# SCH__0_1_2022-09-27.net
KiCad netlist of a schematic drawn in EasyEDA
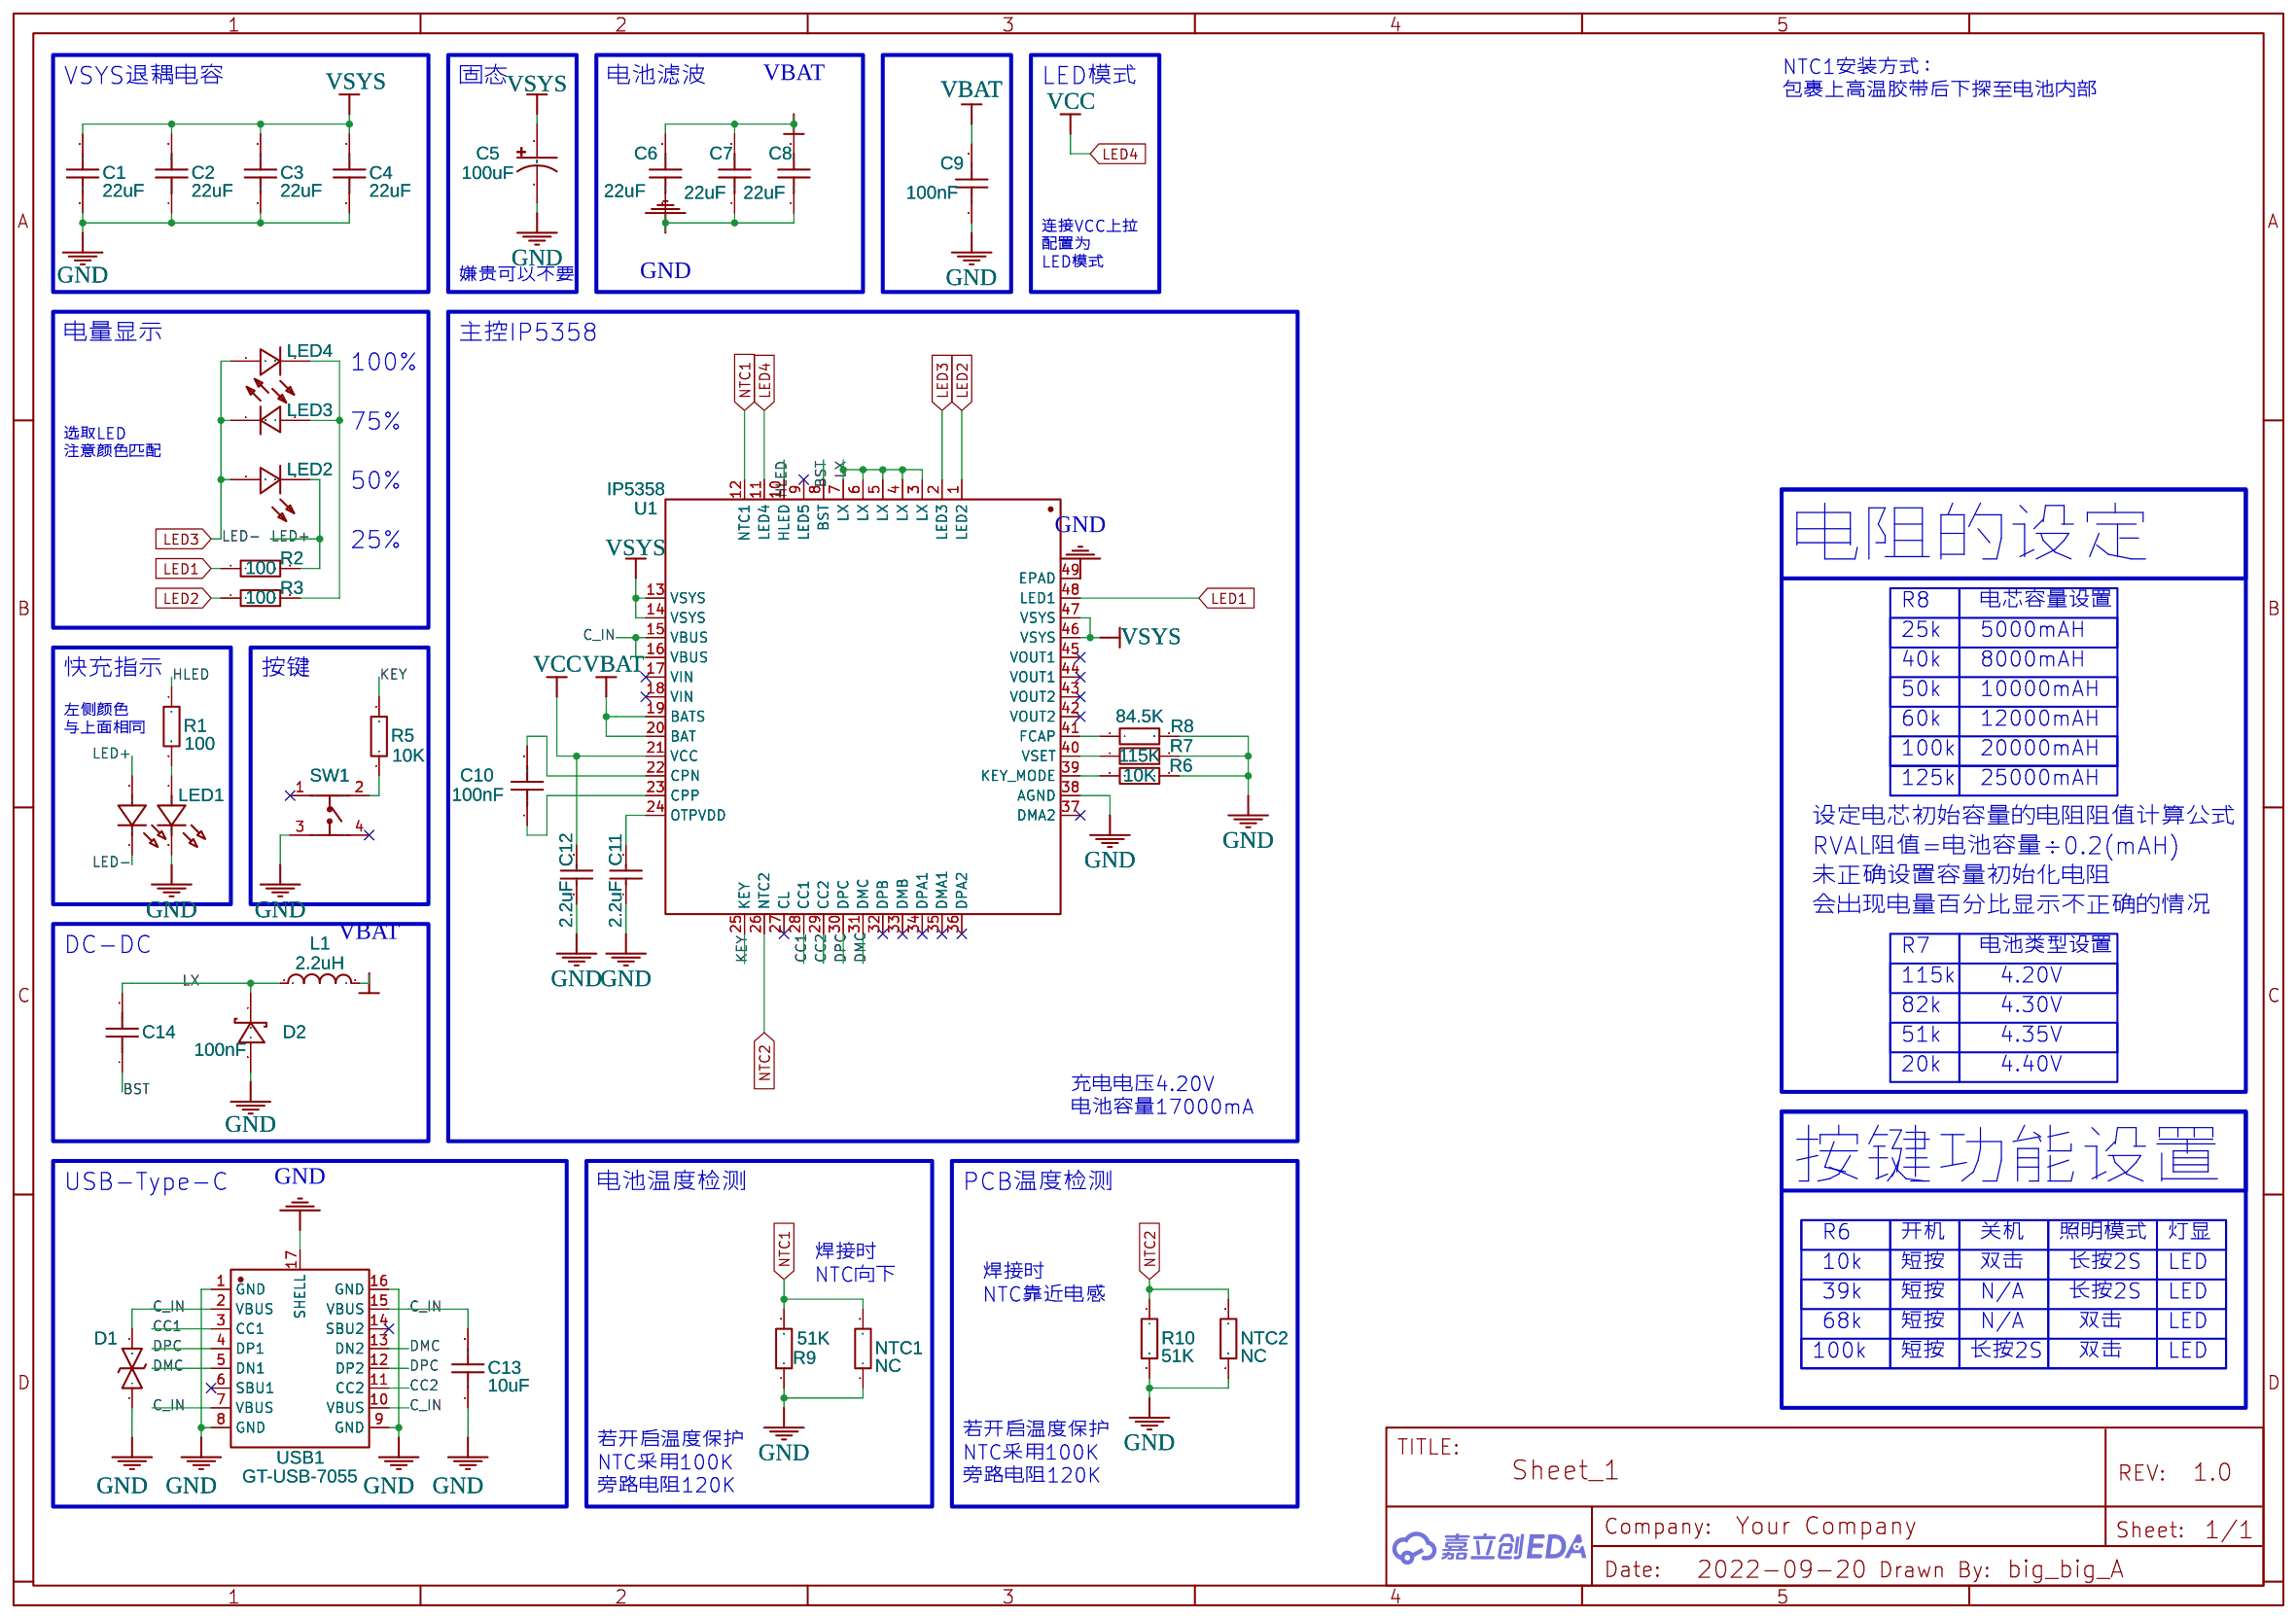
[diagram p0: schematic sheet]

(export (version "E")
  (design (tool "Eeschema 10.0.6"))
  (components
    (comp (ref "C1")
      (value "22uF")
      (fields
        (field (name "BOM_Manufacturer Part") "EMK316ABJ226KL-T")
        (field (name "BOM_Supplier Part") "C319197")
      )
      (libsource (lib "") (part "EMK316ABJ226KL-T"))
    )
    (comp (ref "C2")
      (value "22uF")
      (fields
        (field (name "BOM_Manufacturer Part") "EMK316ABJ226KL-T")
        (field (name "BOM_Supplier Part") "C319197")
      )
      (libsource (lib "") (part "EMK316ABJ226KL-T"))
    )
    (comp (ref "C3")
      (value "22uF")
      (fields
        (field (name "BOM_Manufacturer Part") "EMK316ABJ226KL-T")
        (field (name "BOM_Supplier Part") "C319197")
      )
      (libsource (lib "") (part "EMK316ABJ226KL-T"))
    )
    (comp (ref "C4")
      (value "22uF")
      (fields
        (field (name "BOM_Manufacturer Part") "EMK316ABJ226KL-T")
        (field (name "BOM_Supplier Part") "C319197")
      )
      (libsource (lib "") (part "EMK316ABJ226KL-T_1"))
    )
    (comp (ref "C5")
      (value "100uF")
      (fields
        (field (name "BOM_Manufacturer Part") "SA10JM101A19R55XXX")
        (field (name "BOM_Supplier Part") "C470943")
      )
      (libsource (lib "") (part "SA10JM101A19R55XXX"))
    )
    (comp (ref "C6")
      (value "22uF")
      (fields
        (field (name "BOM_Manufacturer Part") "GRM188R61A226ME15D")
        (field (name "BOM_Supplier Part") "C84419")
      )
      (libsource (lib "") (part "GRM188R61A226ME15D"))
    )
    (comp (ref "C7")
      (value "22uF")
      (fields
        (field (name "BOM_Manufacturer Part") "GRM188R61A226ME15D")
        (field (name "BOM_Supplier Part") "C84419")
      )
      (libsource (lib "") (part "GRM188R61A226ME15D"))
    )
    (comp (ref "C8")
      (value "22uF")
      (fields
        (field (name "BOM_Manufacturer Part") "GRM188R61A226ME15D")
        (field (name "BOM_Supplier Part") "C84419")
      )
      (libsource (lib "") (part "GRM188R61A226ME15D"))
    )
    (comp (ref "C9")
      (value "100nF")
      (fields
        (field (name "BOM_Manufacturer Part") "CL10B104KB8NNNC")
        (field (name "BOM_Supplier Part") "C1591")
      )
      (libsource (lib "") (part "CL10B104KB8NNNC_1"))
    )
    (comp (ref "C10")
      (value "100nF")
      (fields
        (field (name "BOM_Manufacturer Part") "CL10B104KB8NNNC")
        (field (name "BOM_Supplier Part") "C1591")
      )
      (libsource (lib "") (part "CL10B104KB8NNNC"))
    )
    (comp (ref "C11")
      (value "2.2uF")
      (fields
        (field (name "BOM_Manufacturer Part") "CC0603KRX5R7BB225")
        (field (name "BOM_Supplier Part") "C106853")
      )
      (libsource (lib "") (part "CC0603KRX5R7BB225"))
    )
    (comp (ref "C12")
      (value "2.2uF")
      (fields
        (field (name "BOM_Manufacturer Part") "CC0603KRX5R7BB225")
        (field (name "BOM_Supplier Part") "C106853")
      )
      (libsource (lib "") (part "CC0603KRX5R7BB225"))
    )
    (comp (ref "C13")
      (value "10uF")
      (fields
        (field (name "BOM_Manufacturer Part") "GRM188R61E106MA73D")
        (field (name "BOM_Supplier Part") "C91606")
      )
      (libsource (lib "") (part "GRM188R61E106MA73D"))
    )
    (comp (ref "C14")
      (value "100nF")
      (fields
        (field (name "BOM_Manufacturer Part") "CL10B104KB8NNNC")
        (field (name "BOM_Supplier Part") "C1591")
      )
      (libsource (lib "") (part "CL10B104KB8NNNC"))
    )
    (comp (ref "D1")
      (value "SMF18CA_C435488")
      (fields (field (name "BOM_Manufacturer Part") "SMF18CA") (field (name "BOM_Supplier Part") "C435488"))
      (libsource (lib "") (part "SMF18CA_C435488"))
    )
    (comp (ref "D2")
      (value "SS34_C408258")
      (fields (field (name "BOM_Manufacturer Part") "SS34") (field (name "BOM_Supplier Part") "C408258"))
      (libsource (lib "") (part "SS34_C408258"))
    )
    (comp (ref "L1")
      (value "2.2uH")
      (fields
        (field (name "BOM_Manufacturer Part") "SLO0650H2R2MTT")
        (field (name "BOM_Supplier Part") "C216163")
      )
      (libsource (lib "") (part "SLO0624H2R2MTT"))
    )
    (comp (ref "LED1")
      (value "红黄绿双色LED")
      (fields (field (name "BOM_Supplier Part") "C9900023609"))
      (libsource (lib "") (part "红黄绿双色LED"))
    )
    (comp (ref "LED2")
      (value "BL-HGE37A-AV-TRB")
      (fields (field (name "BOM_Supplier Part") "C165979"))
      (libsource (lib "") (part "BL-HGE37A-AV-TRB"))
    )
    (comp (ref "LED3")
      (value "BL-HGE37A-AV-TRB")
      (fields (field (name "BOM_Supplier Part") "C165979"))
      (libsource (lib "") (part "BL-HGE37A-AV-TRB_1"))
    )
    (comp (ref "LED4")
      (value "BL-HGE37A-AV-TRB")
      (fields (field (name "BOM_Supplier Part") "C165979"))
      (libsource (lib "") (part "BL-HGE37A-AV-TRB"))
    )
    (comp (ref "NTC1")
      (value "NC")
      (fields
        (field (name "BOM_Manufacturer Part") "NTC-100K")
        (field (name "BOM_Supplier Part") "C9900024696")
      )
      (libsource (lib "") (part "NTC-100K"))
    )
    (comp (ref "NTC2")
      (value "NC")
      (fields
        (field (name "BOM_Manufacturer Part") "NTC-100K")
        (field (name "BOM_Supplier Part") "C9900024696")
      )
      (libsource (lib "") (part "NTC-100K"))
    )
    (comp (ref "R1")
      (value "100")
      (fields
        (field (name "BOM_Manufacturer Part") "0603WAF1000T5E")
        (field (name "BOM_Supplier Part") "C22775")
      )
      (libsource (lib "") (part "0603WAF1000T5E_1"))
    )
    (comp (ref "R2")
      (value "100")
      (fields
        (field (name "BOM_Manufacturer Part") "0603WAF1000T5E")
        (field (name "BOM_Supplier Part") "C22775")
      )
      (libsource (lib "") (part "0603WAF1000T5E"))
    )
    (comp (ref "R3")
      (value "100")
      (fields
        (field (name "BOM_Manufacturer Part") "0603WAF1000T5E")
        (field (name "BOM_Supplier Part") "C22775")
      )
      (libsource (lib "") (part "0603WAF1000T5E"))
    )
    (comp (ref "R5")
      (value "10K")
      (fields
        (field (name "BOM_Manufacturer Part") "0603WAF1000T5E")
        (field (name "BOM_Supplier Part") "C22775")
      )
      (libsource (lib "") (part "0603WAF1000T5E_1"))
    )
    (comp (ref "R6")
      (value "10K")
      (fields
        (field (name "BOM_Manufacturer Part") "RMCF0603JT10K0")
        (field (name "BOM_Supplier Part") "C238881")
      )
      (libsource (lib "") (part "RMCF0603JT10K0"))
    )
    (comp (ref "R7")
      (value "115K")
      (fields
        (field (name "BOM_Manufacturer Part") "RC0603FR-07115KL")
        (field (name "BOM_Supplier Part") "C137806")
      )
      (libsource (lib "") (part "RC0603FR-07115KL"))
    )
    (comp (ref "R8")
      (value "84.5K")
      (fields
        (field (name "BOM_Manufacturer Part") "RK73H1JTTD5102F")
        (field (name "BOM_Supplier Part") "C160049")
      )
      (libsource (lib "") (part "RK73H1JTTD5102F"))
    )
    (comp (ref "R9")
      (value "51K")
      (fields
        (field (name "BOM_Manufacturer Part") "0603WAF5102T5E")
        (field (name "BOM_Supplier Part") "C23196")
      )
      (libsource (lib "") (part "0603WAF5102T5E_1"))
    )
    (comp (ref "R10")
      (value "51K")
      (fields
        (field (name "BOM_Manufacturer Part") "0603WAF5102T5E")
        (field (name "BOM_Supplier Part") "C23196")
      )
      (libsource (lib "") (part "0603WAF5102T5E"))
    )
    (comp (ref "SW1")
      (value "TC-1150DR-6.0H-160")
      (fields (field (name "BOM_Supplier Part") "C2905090"))
      (libsource (lib "") (part "TC-1150DR-6.0H-160"))
    )
    (comp (ref "U1")
      (value "IP5358")
      (fields (field (name "BOM_Manufacturer Part") "IP5358-BZ") (field (name "BOM_Supplier Part") "C879824"))
      (libsource (lib "") (part "IP5358"))
    )
    (comp (ref "USB1")
      (value "GT-USB-7055")
      (fields (field (name "BOM_Supplier Part") "C2686963"))
      (libsource (lib "") (part "GT-USB-7055"))
    )
  )
  (nets
    (net (code "1") (name "/BST") (class "Default")
      (node (ref "C14") (pin "1") (pinfunction "1_1") (pintype "unspecified"))
      (node (ref "U1") (pin "8") (pinfunction "BST_8") (pintype "unspecified"))
    )
    (net (code "2") (name "/CC1") (class "Default")
      (node (ref "U1") (pin "28") (pinfunction "CC1_28") (pintype "unspecified"))
      (node (ref "USB1") (pin "3") (pinfunction "CC1_3") (pintype "unspecified"))
    )
    (net (code "3") (name "/CC2") (class "Default")
      (node (ref "U1") (pin "29") (pinfunction "CC2_29") (pintype "unspecified"))
      (node (ref "USB1") (pin "11") (pinfunction "CC2_11") (pintype "unspecified"))
    )
    (net (code "4") (name "/C_IN") (class "Default")
      (node (ref "C13") (pin "2") (pinfunction "2_2") (pintype "unspecified"))
      (node (ref "D1") (pin "2") (pinfunction "2_2") (pintype "unspecified"))
      (node (ref "U1") (pin "15") (pinfunction "VBUS_15") (pintype "unspecified"))
      (node (ref "U1") (pin "16") (pinfunction "VBUS_16") (pintype "unspecified"))
      (node (ref "USB1") (pin "10") (pinfunction "VBUS_10") (pintype "unspecified"))
      (node (ref "USB1") (pin "15") (pinfunction "VBUS_15") (pintype "unspecified"))
      (node (ref "USB1") (pin "2") (pinfunction "VBUS_2") (pintype "unspecified"))
      (node (ref "USB1") (pin "7") (pinfunction "VBUS_7") (pintype "unspecified"))
    )
    (net (code "5") (name "/DMC") (class "Default")
      (node (ref "U1") (pin "31") (pinfunction "DMC_31") (pintype "unspecified"))
      (node (ref "USB1") (pin "13") (pinfunction "DN2_13") (pintype "unspecified"))
      (node (ref "USB1") (pin "5") (pinfunction "DN1_5") (pintype "unspecified"))
    )
    (net (code "6") (name "/DPC") (class "Default")
      (node (ref "U1") (pin "30") (pinfunction "DPC_30") (pintype "unspecified"))
      (node (ref "USB1") (pin "12") (pinfunction "DP2_12") (pintype "unspecified"))
      (node (ref "USB1") (pin "4") (pinfunction "DP1_4") (pintype "unspecified"))
    )
    (net (code "7") (name "/HLED") (class "Default")
      (node (ref "R1") (pin "1") (pinfunction "1_1") (pintype "input"))
      (node (ref "U1") (pin "10") (pinfunction "HLED_10") (pintype "unspecified"))
    )
    (net (code "8") (name "/KEY") (class "Default")
      (node (ref "R5") (pin "1") (pinfunction "1_1") (pintype "input"))
      (node (ref "U1") (pin "25") (pinfunction "KEY_25") (pintype "unspecified"))
    )
    (net (code "9") (name "/LED+") (class "Default")
      (node (ref "LED1") (pin "3") (pinfunction "3_3") (pintype "unspecified"))
      (node (ref "LED2") (pin "1") (pinfunction "C_1") (pintype "unspecified"))
      (node (ref "R2") (pin "2") (pinfunction "2_2") (pintype "input"))
    )
    (net (code "10") (name "/LX") (class "Default")
      (node (ref "C14") (pin "2") (pinfunction "2_2") (pintype "unspecified"))
      (node (ref "D2") (pin "1") (pinfunction "C_1") (pintype "unspecified"))
      (node (ref "L1") (pin "1") (pinfunction "1_1") (pintype "unspecified"))
      (node (ref "U1") (pin "3") (pinfunction "LX_3") (pintype "unspecified"))
      (node (ref "U1") (pin "4") (pinfunction "LX_4") (pintype "unspecified"))
      (node (ref "U1") (pin "5") (pinfunction "LX_5") (pintype "unspecified"))
      (node (ref "U1") (pin "6") (pinfunction "LX_6") (pintype "unspecified"))
      (node (ref "U1") (pin "7") (pinfunction "LX_7") (pintype "unspecified"))
    )
    (net (code "11") (name "GND") (class "Default")
      (node (ref "C1") (pin "1") (pinfunction "1_1") (pintype "unspecified"))
      (node (ref "C11") (pin "1") (pinfunction "1_1") (pintype "input"))
      (node (ref "C12") (pin "1") (pinfunction "1_1") (pintype "input"))
      (node (ref "C13") (pin "1") (pinfunction "1_1") (pintype "unspecified"))
      (node (ref "C2") (pin "1") (pinfunction "1_1") (pintype "unspecified"))
      (node (ref "C3") (pin "1") (pinfunction "1_1") (pintype "unspecified"))
      (node (ref "C4") (pin "2") (pinfunction "2_2") (pintype "unspecified"))
      (node (ref "C5") (pin "2") (pinfunction "2_2") (pintype "unspecified"))
      (node (ref "C6") (pin "1") (pinfunction "1_1") (pintype "unspecified"))
      (node (ref "C7") (pin "1") (pinfunction "1_1") (pintype "unspecified"))
      (node (ref "C8") (pin "1") (pinfunction "1_1") (pintype "unspecified"))
      (node (ref "C9") (pin "2") (pinfunction "2_2") (pintype "unspecified"))
      (node (ref "D1") (pin "1") (pinfunction "1_1") (pintype "unspecified"))
      (node (ref "D2") (pin "2") (pinfunction "A_2") (pintype "unspecified"))
      (node (ref "LED1") (pin "2") (pinfunction "2_2") (pintype "unspecified"))
      (node (ref "NTC1") (pin "1") (pinfunction "1_1") (pintype "unspecified"))
      (node (ref "NTC2") (pin "1") (pinfunction "1_1") (pintype "unspecified"))
      (node (ref "R10") (pin "2") (pinfunction "2_2") (pintype "input"))
      (node (ref "R6") (pin "1") (pinfunction "1_1") (pintype "unspecified"))
      (node (ref "R7") (pin "2") (pinfunction "2_2") (pintype "input"))
      (node (ref "R8") (pin "2") (pinfunction "2_2") (pintype "unspecified"))
      (node (ref "R9") (pin "1") (pinfunction "1_1") (pintype "input"))
      (node (ref "SW1") (pin "3") (pinfunction "3_3") (pintype "unspecified"))
      (node (ref "U1") (pin "38") (pinfunction "AGND_38") (pintype "unspecified"))
      (node (ref "U1") (pin "49") (pinfunction "EPAD_49") (pintype "unspecified"))
      (node (ref "USB1") (pin "1") (pinfunction "GND_1") (pintype "unspecified"))
      (node (ref "USB1") (pin "16") (pinfunction "GND_16") (pintype "unspecified"))
      (node (ref "USB1") (pin "17") (pinfunction "SHELL_17") (pintype "unspecified"))
      (node (ref "USB1") (pin "8") (pinfunction "GND_8") (pintype "unspecified"))
      (node (ref "USB1") (pin "9") (pinfunction "GND_9") (pintype "unspecified"))
    )
    (net (code "12") (name "LED1") (class "Default")
      (node (ref "R2") (pin "1") (pinfunction "1_1") (pintype "input"))
      (node (ref "U1") (pin "48") (pinfunction "LED1_48") (pintype "unspecified"))
    )
    (net (code "13") (name "LED2") (class "Default")
      (node (ref "R3") (pin "1") (pinfunction "1_1") (pintype "input"))
      (node (ref "U1") (pin "1") (pinfunction "LED2_1") (pintype "unspecified"))
    )
    (net (code "14") (name "LED3") (class "Default")
      (node (ref "LED1") (pin "4") (pinfunction "4_4") (pintype "unspecified"))
      (node (ref "LED2") (pin "2") (pinfunction "A_2") (pintype "unspecified"))
      (node (ref "LED3") (pin "1") (pinfunction "C_1") (pintype "unspecified"))
      (node (ref "LED4") (pin "2") (pinfunction "A_2") (pintype "unspecified"))
      (node (ref "U1") (pin "2") (pinfunction "LED3_2") (pintype "unspecified"))
    )
    (net (code "15") (name "LED4") (class "Default")
      (node (ref "C12") (pin "2") (pinfunction "2_2") (pintype "input"))
      (node (ref "U1") (pin "11") (pinfunction "LED4_11") (pintype "unspecified"))
      (node (ref "U1") (pin "21") (pinfunction "VCC_21") (pintype "unspecified"))
    )
    (net (code "16") (name "NTC1") (class "Default")
      (node (ref "NTC1") (pin "2") (pinfunction "2_2") (pintype "unspecified"))
      (node (ref "R9") (pin "2") (pinfunction "2_2") (pintype "input"))
      (node (ref "U1") (pin "12") (pinfunction "NTC1_12") (pintype "unspecified"))
    )
    (net (code "17") (name "NTC2") (class "Default")
      (node (ref "NTC2") (pin "2") (pinfunction "2_2") (pintype "unspecified"))
      (node (ref "R10") (pin "1") (pinfunction "1_1") (pintype "input"))
      (node (ref "U1") (pin "26") (pinfunction "NTC2_26") (pintype "unspecified"))
    )
    (net (code "18") (name "Net-(LED1-Pad1)") (class "Default")
      (node (ref "LED1") (pin "1") (pinfunction "1_1") (pintype "unspecified"))
      (node (ref "R1") (pin "2") (pinfunction "2_2") (pintype "input"))
    )
    (net (code "19") (name "Net-(LED3-A)") (class "Default")
      (node (ref "LED3") (pin "2") (pinfunction "A_2") (pintype "unspecified"))
      (node (ref "LED4") (pin "1") (pinfunction "C_1") (pintype "unspecified"))
      (node (ref "R3") (pin "2") (pinfunction "2_2") (pintype "input"))
    )
    (net (code "20") (name "Net-(R5-Pad2)") (class "Default")
      (node (ref "R5") (pin "2") (pinfunction "2_2") (pintype "input"))
      (node (ref "SW1") (pin "2") (pinfunction "2_2") (pintype "unspecified"))
    )
    (net (code "21") (name "Net-(U1-CPN)") (class "Default")
      (node (ref "C10") (pin "2") (pinfunction "2_2") (pintype "unspecified"))
      (node (ref "U1") (pin "22") (pinfunction "CPN_22") (pintype "unspecified"))
    )
    (net (code "22") (name "Net-(U1-CPP)") (class "Default")
      (node (ref "C10") (pin "1") (pinfunction "1_1") (pintype "unspecified"))
      (node (ref "U1") (pin "23") (pinfunction "CPP_23") (pintype "unspecified"))
    )
    (net (code "23") (name "Net-(U1-FCAP)") (class "Default")
      (node (ref "R8") (pin "1") (pinfunction "1_1") (pintype "unspecified"))
      (node (ref "U1") (pin "41") (pinfunction "FCAP_41") (pintype "unspecified"))
    )
    (net (code "24") (name "Net-(U1-KEY_MODE)") (class "Default")
      (node (ref "R6") (pin "2") (pinfunction "2_2") (pintype "unspecified"))
      (node (ref "U1") (pin "39") (pinfunction "KEY_MODE_39") (pintype "unspecified"))
    )
    (net (code "25") (name "Net-(U1-OTPVDD)") (class "Default")
      (node (ref "C11") (pin "2") (pinfunction "2_2") (pintype "input"))
      (node (ref "U1") (pin "24") (pinfunction "OTPVDD_24") (pintype "unspecified"))
    )
    (net (code "26") (name "Net-(U1-VSET)") (class "Default")
      (node (ref "R7") (pin "1") (pinfunction "1_1") (pintype "input"))
      (node (ref "U1") (pin "40") (pinfunction "VSET_40") (pintype "unspecified"))
    )
    (net (code "27") (name "VBAT") (class "Default")
      (node (ref "C6") (pin "2") (pinfunction "2_2") (pintype "unspecified"))
      (node (ref "C7") (pin "2") (pinfunction "2_2") (pintype "unspecified"))
      (node (ref "C8") (pin "2") (pinfunction "2_2") (pintype "unspecified"))
      (node (ref "C9") (pin "1") (pinfunction "1_1") (pintype "unspecified"))
      (node (ref "L1") (pin "2") (pinfunction "2_2") (pintype "unspecified"))
      (node (ref "U1") (pin "19") (pinfunction "BATS_19") (pintype "unspecified"))
      (node (ref "U1") (pin "20") (pinfunction "BAT_20") (pintype "unspecified"))
    )
    (net (code "28") (name "VSYS") (class "Default")
      (node (ref "C1") (pin "2") (pinfunction "2_2") (pintype "unspecified"))
      (node (ref "C2") (pin "2") (pinfunction "2_2") (pintype "unspecified"))
      (node (ref "C3") (pin "2") (pinfunction "2_2") (pintype "unspecified"))
      (node (ref "C4") (pin "1") (pinfunction "1_1") (pintype "unspecified"))
      (node (ref "C5") (pin "1") (pinfunction "1_1") (pintype "unspecified"))
      (node (ref "U1") (pin "13") (pinfunction "VSYS_13") (pintype "unspecified"))
      (node (ref "U1") (pin "14") (pinfunction "VSYS_14") (pintype "unspecified"))
      (node (ref "U1") (pin "46") (pinfunction "VSYS_46") (pintype "unspecified"))
      (node (ref "U1") (pin "47") (pinfunction "VSYS_47") (pintype "unspecified"))
    )
    (net (code "29") (name "unconnected-(SW1-Pad1)") (class "Default")
      (node (ref "SW1") (pin "1") (pinfunction "1_1") (pintype "unspecified+no_connect"))
    )
    (net (code "30") (name "unconnected-(SW1-Pad4)") (class "Default")
      (node (ref "SW1") (pin "4") (pinfunction "4_4") (pintype "unspecified+no_connect"))
    )
    (net (code "31") (name "unconnected-(U1-CL-Pad27)") (class "Default")
      (node (ref "U1") (pin "27") (pinfunction "CL_27") (pintype "unspecified+no_connect"))
    )
    (net (code "32") (name "unconnected-(U1-DMA1-Pad35)") (class "Default")
      (node (ref "U1") (pin "35") (pinfunction "DMA1_35") (pintype "unspecified+no_connect"))
    )
    (net (code "33") (name "unconnected-(U1-DMA2-Pad37)") (class "Default")
      (node (ref "U1") (pin "37") (pinfunction "DMA2_37") (pintype "unspecified+no_connect"))
    )
    (net (code "34") (name "unconnected-(U1-DMB-Pad33)") (class "Default")
      (node (ref "U1") (pin "33") (pinfunction "DMB_33") (pintype "unspecified+no_connect"))
    )
    (net (code "35") (name "unconnected-(U1-DPA1-Pad34)") (class "Default")
      (node (ref "U1") (pin "34") (pinfunction "DPA1_34") (pintype "unspecified+no_connect"))
    )
    (net (code "36") (name "unconnected-(U1-DPA2-Pad36)") (class "Default")
      (node (ref "U1") (pin "36") (pinfunction "DPA2_36") (pintype "unspecified+no_connect"))
    )
    (net (code "37") (name "unconnected-(U1-DPB-Pad32)") (class "Default")
      (node (ref "U1") (pin "32") (pinfunction "DPB_32") (pintype "unspecified+no_connect"))
    )
    (net (code "38") (name "unconnected-(U1-LED5-Pad9)") (class "Default")
      (node (ref "U1") (pin "9") (pinfunction "LED5_9") (pintype "unspecified+no_connect"))
    )
    (net (code "39") (name "unconnected-(U1-VIN-Pad17)") (class "Default")
      (node (ref "U1") (pin "17") (pinfunction "VIN_17") (pintype "unspecified+no_connect"))
    )
    (net (code "40") (name "unconnected-(U1-VIN-Pad18)") (class "Default")
      (node (ref "U1") (pin "18") (pinfunction "VIN_18") (pintype "unspecified+no_connect"))
    )
    (net (code "41") (name "unconnected-(U1-VOUT1-Pad44)") (class "Default")
      (node (ref "U1") (pin "44") (pinfunction "VOUT1_44") (pintype "unspecified+no_connect"))
    )
    (net (code "42") (name "unconnected-(U1-VOUT1-Pad45)") (class "Default")
      (node (ref "U1") (pin "45") (pinfunction "VOUT1_45") (pintype "unspecified+no_connect"))
    )
    (net (code "43") (name "unconnected-(U1-VOUT2-Pad42)") (class "Default")
      (node (ref "U1") (pin "42") (pinfunction "VOUT2_42") (pintype "unspecified+no_connect"))
    )
    (net (code "44") (name "unconnected-(U1-VOUT2-Pad43)") (class "Default")
      (node (ref "U1") (pin "43") (pinfunction "VOUT2_43") (pintype "unspecified+no_connect"))
    )
    (net (code "45") (name "unconnected-(USB1-SBU1-Pad6)") (class "Default")
      (node (ref "USB1") (pin "6") (pinfunction "SBU1_6") (pintype "unspecified+no_connect"))
    )
    (net (code "46") (name "unconnected-(USB1-SBU2-Pad14)") (class "Default")
      (node (ref "USB1") (pin "14") (pinfunction "SBU2_14") (pintype "unspecified+no_connect"))
    )
  )
)
